# Zio_Ultrasonic_Distance_Sensor.net
KiCad netlist of a schematic drawn in EAGLE
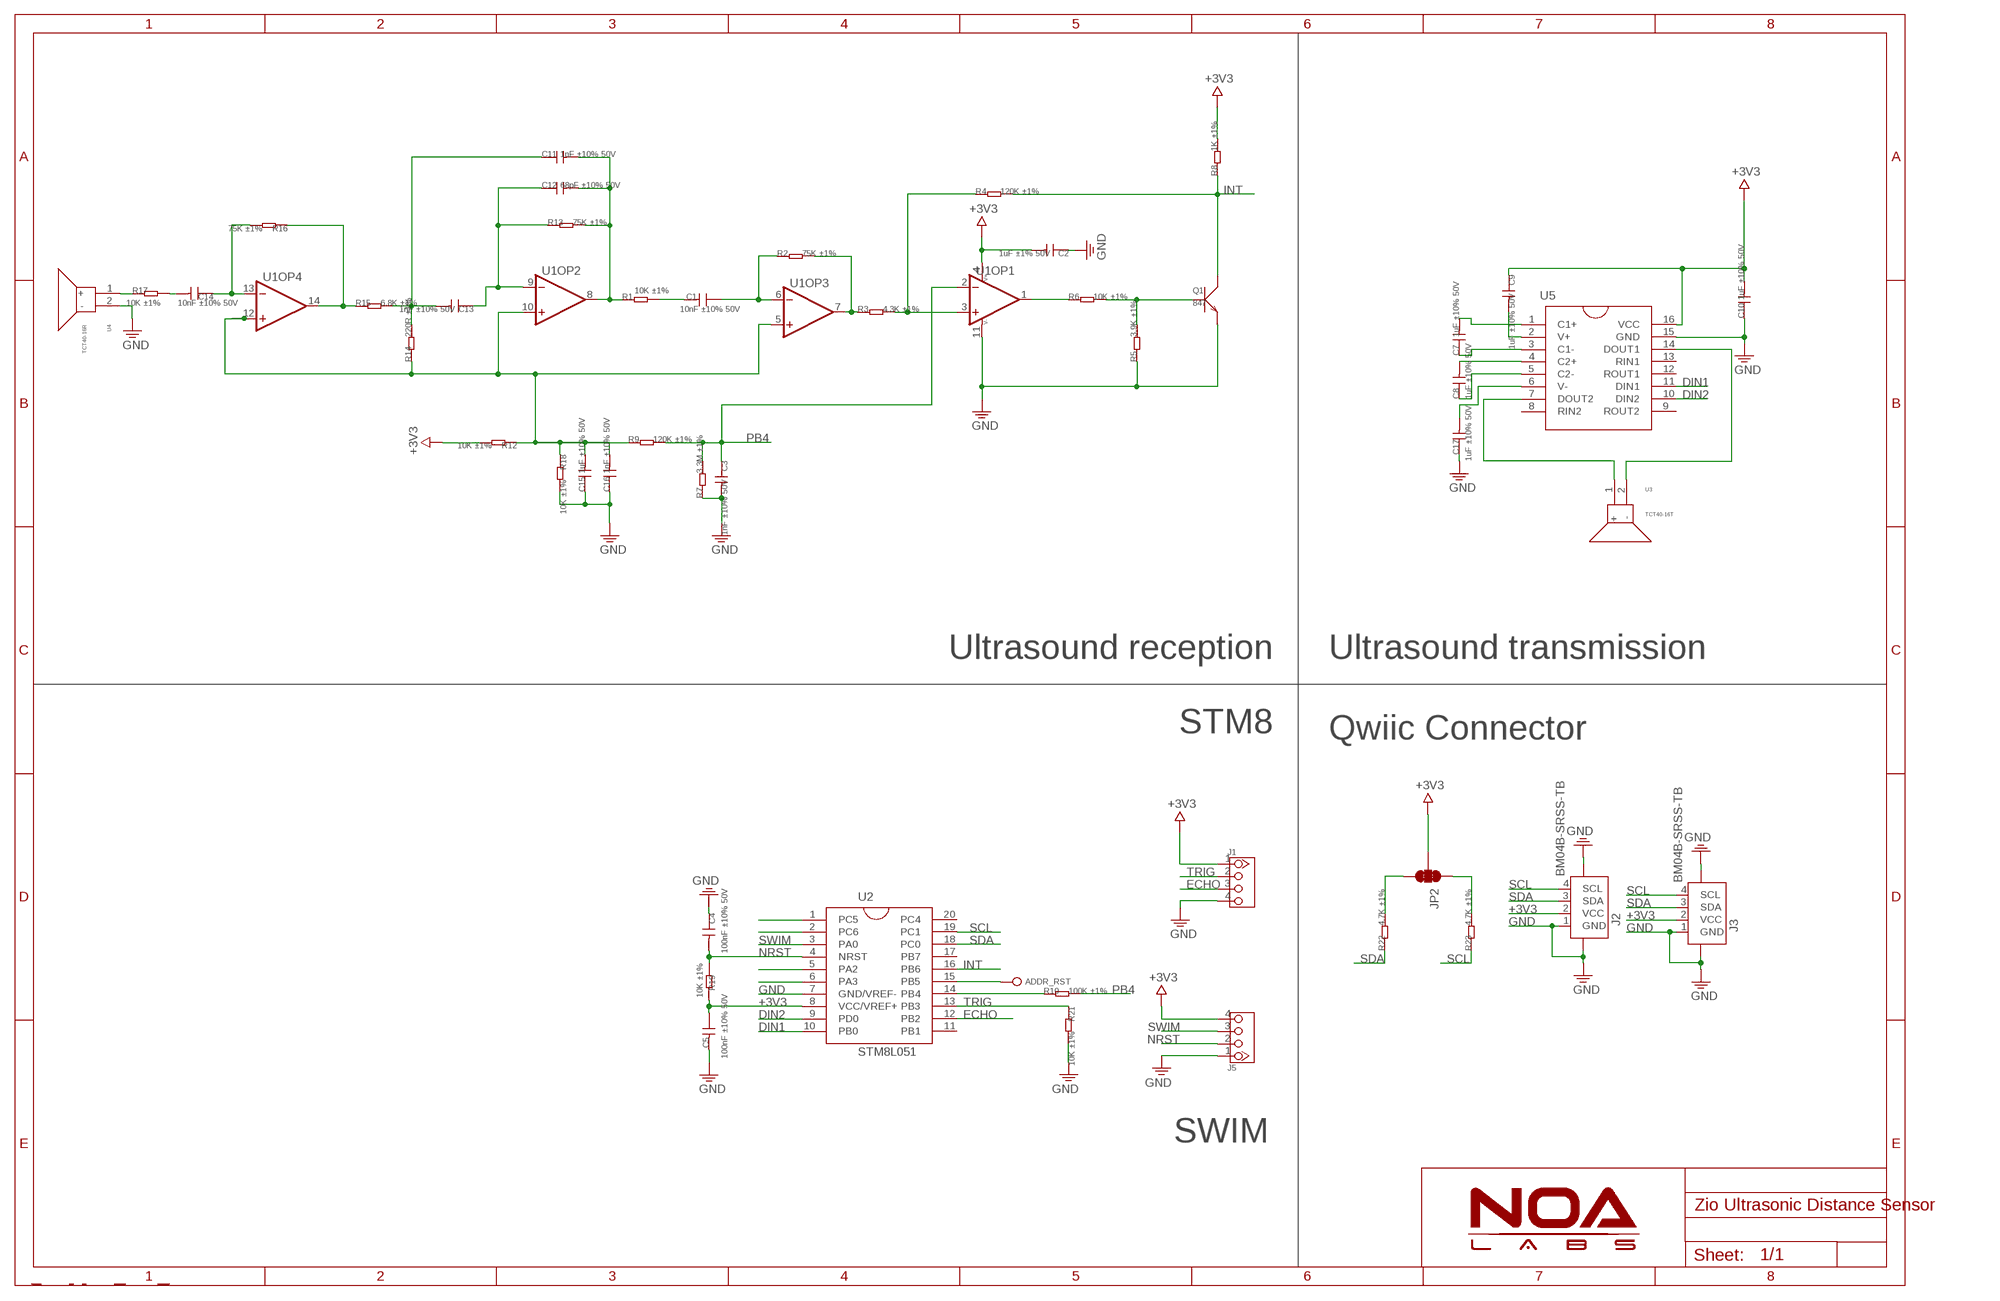
[diagram p0: schematic, sheet 1]

(export (version "E")
  (design (tool "Eeschema 10.0.6"))
  (components
    (comp (ref "ADDR_RST")
      (value "TEST_POINT35MIL")
      (footprint "eagle-import:1P-35MIL")
      (libsource (lib "eagle-import") (part "TEST_POINT35MIL"))
    )
    (comp (ref "C1")
      (value "10nF ±10% 50V")
      (footprint "eagle-import:0603")
      (libsource (lib "eagle-import") (part "C-0603"))
    )
    (comp (ref "C2")
      (value "1uF ±1% 50V")
      (footprint "eagle-import:0603")
      (libsource (lib "eagle-import") (part "C-0603"))
    )
    (comp (ref "C3")
      (value "1nF ±10% 50V")
      (footprint "eagle-import:0603")
      (libsource (lib "eagle-import") (part "C-0603"))
    )
    (comp (ref "C4")
      (value "100nF ±10% 50V")
      (footprint "eagle-import:0603")
      (libsource (lib "eagle-import") (part "C-0603"))
    )
    (comp (ref "C5")
      (value "100nF ±10% 50V")
      (footprint "eagle-import:0603")
      (libsource (lib "eagle-import") (part "C-0603"))
    )
    (comp (ref "C7")
      (value "1uF ±10% 50V")
      (footprint "eagle-import:0603")
      (libsource (lib "eagle-import") (part "C-0603"))
    )
    (comp (ref "C8")
      (value "1uF ±10% 50V")
      (footprint "eagle-import:0603")
      (libsource (lib "eagle-import") (part "C-0603"))
    )
    (comp (ref "C9")
      (value "1uF ±10% 50V")
      (footprint "eagle-import:0603")
      (libsource (lib "eagle-import") (part "C-0603"))
    )
    (comp (ref "C10")
      (value "1uF ±10% 50V")
      (footprint "eagle-import:0603")
      (libsource (lib "eagle-import") (part "C-0603"))
    )
    (comp (ref "C11")
      (value "1nF ±10% 50V")
      (footprint "eagle-import:0603")
      (libsource (lib "eagle-import") (part "C-0603"))
    )
    (comp (ref "C12")
      (value "68pF ±10% 50V")
      (footprint "eagle-import:0603")
      (libsource (lib "eagle-import") (part "C-0603"))
    )
    (comp (ref "C13")
      (value "1nF ±10% 50V")
      (footprint "eagle-import:0603")
      (libsource (lib "eagle-import") (part "C-0603"))
    )
    (comp (ref "C14")
      (value "10nF ±10% 50V")
      (footprint "eagle-import:0603")
      (libsource (lib "eagle-import") (part "C-0603"))
    )
    (comp (ref "C15")
      (value "1uF ±10% 50V")
      (footprint "eagle-import:0603")
      (libsource (lib "eagle-import") (part "C-0603"))
    )
    (comp (ref "C16")
      (value "1nF ±10% 50V")
      (footprint "eagle-import:0603")
      (libsource (lib "eagle-import") (part "C-0603"))
    )
    (comp (ref "C17")
      (value "1uF ±10% 50V")
      (footprint "eagle-import:0603")
      (libsource (lib "eagle-import") (part "C-0603"))
    )
    (comp (ref "J1")
      (value "HEADER-4P-60/35MIL")
      (footprint "eagle-import:4P-65_35MIL")
      (libsource (lib "eagle-import") (part "HEADER-4P-60/35MIL"))
    )
    (comp (ref "J2")
      (value "BM04B-SRSS-TB")
      (footprint "eagle-import:JST-SH-4P-90")
      (libsource (lib "eagle-import") (part "JST-SH-4P"))
    )
    (comp (ref "J3")
      (value "BM04B-SRSS-TB")
      (footprint "eagle-import:JST-SH-4P-90")
      (libsource (lib "eagle-import") (part "JST-SH-4P"))
    )
    (comp (ref "J5")
      (value "HEADER-4P-TEST_3.08_4P")
      (footprint "eagle-import:TEST_3.08_4P")
      (libsource (lib "eagle-import") (part "HEADER-4P-TEST_3.08_4P"))
    )
    (comp (ref "JP2")
      (value "SMT-JUMPER_3_2-NC_TRACE")
      (footprint "eagle-import:SMT-JUMPER_3_2-NC_TRACE")
      (libsource (lib "eagle-import") (part "SMT-JUMPER_3_2-NC_TRACE"))
    )
    (comp (ref "Q1")
      (value "847")
      (footprint "eagle-import:SOT23")
      (libsource (lib "eagle-import") (part "TRANSISTOR-NPN-SOT23''"))
    )
    (comp (ref "R1")
      (value "10K ±1%")
      (footprint "eagle-import:0603")
      (libsource (lib "eagle-import") (part "R-0603"))
    )
    (comp (ref "R2")
      (value "75K ±1%")
      (footprint "eagle-import:0603")
      (libsource (lib "eagle-import") (part "R-0603"))
    )
    (comp (ref "R3")
      (value "4.3K ±1%")
      (footprint "eagle-import:0603")
      (libsource (lib "eagle-import") (part "R-0603"))
    )
    (comp (ref "R4")
      (value "120K ±1%")
      (footprint "eagle-import:0603")
      (libsource (lib "eagle-import") (part "R-0603"))
    )
    (comp (ref "R5")
      (value "3.9K ±1%")
      (footprint "eagle-import:0603")
      (libsource (lib "eagle-import") (part "R-0603"))
    )
    (comp (ref "R6")
      (value "10K ±1%")
      (footprint "eagle-import:0603")
      (libsource (lib "eagle-import") (part "R-0603"))
    )
    (comp (ref "R7")
      (value "3.3M ±1%")
      (footprint "eagle-import:0603")
      (libsource (lib "eagle-import") (part "R-0603"))
    )
    (comp (ref "R8")
      (value "1K ±1%")
      (footprint "eagle-import:0603")
      (libsource (lib "eagle-import") (part "R-0603"))
    )
    (comp (ref "R9")
      (value "120K ±1%")
      (footprint "eagle-import:0603")
      (libsource (lib "eagle-import") (part "R-0603"))
    )
    (comp (ref "R10")
      (value "100K ±1%")
      (footprint "eagle-import:0603")
      (libsource (lib "eagle-import") (part "R-0603"))
    )
    (comp (ref "R12")
      (value "10K ±1%")
      (footprint "eagle-import:0603")
      (libsource (lib "eagle-import") (part "R-0603"))
    )
    (comp (ref "R13")
      (value "75K ±1%")
      (footprint "eagle-import:0603")
      (libsource (lib "eagle-import") (part "R-0603"))
    )
    (comp (ref "R14")
      (value "220R ±1%")
      (footprint "eagle-import:0603")
      (libsource (lib "eagle-import") (part "R-0603"))
    )
    (comp (ref "R15")
      (value "6.8K ±1%")
      (footprint "eagle-import:0603")
      (libsource (lib "eagle-import") (part "R-0603"))
    )
    (comp (ref "R16")
      (value "75K ±1%")
      (footprint "eagle-import:0603")
      (libsource (lib "eagle-import") (part "R-0603"))
    )
    (comp (ref "R17")
      (value "10K ±1%")
      (footprint "eagle-import:0603")
      (libsource (lib "eagle-import") (part "R-0603"))
    )
    (comp (ref "R18")
      (value "10K ±1%")
      (footprint "eagle-import:0603")
      (libsource (lib "eagle-import") (part "R-0603"))
    )
    (comp (ref "R19")
      (value "10K ±1%")
      (footprint "eagle-import:0603")
      (libsource (lib "eagle-import") (part "R-0603"))
    )
    (comp (ref "R21")
      (value "10K ±1%")
      (footprint "eagle-import:0603")
      (libsource (lib "eagle-import") (part "R-0603"))
    )
    (comp (ref "R22")
      (value "4.7K ±1%")
      (footprint "eagle-import:0603")
      (libsource (lib "eagle-import") (part "R-0603"))
    )
    (comp (ref "R23")
      (value "4.7K ±1%")
      (footprint "eagle-import:0603")
      (libsource (lib "eagle-import") (part "R-0603"))
    )
    (comp (ref "U1")
      (value "LMV324")
      (footprint "eagle-import:SO014")
      (libsource (lib "eagle-import") (part "LMV324"))
    )
    (comp (ref "U2")
      (value "STM8L051")
      (footprint "eagle-import:TSSOP20")
      (libsource (lib "eagle-import") (part "STM8L051"))
    )
    (comp (ref "U3")
      (value "TCT40-16T")
      (footprint "eagle-import:TCT40-16T_R")
      (libsource (lib "eagle-import") (part "TCT40-16T/R"))
    )
    (comp (ref "U4")
      (value "TCT40-16R")
      (footprint "eagle-import:TCT40-16T_R")
      (libsource (lib "eagle-import") (part "TCT40-16T/R"))
    )
    (comp (ref "U5")
      (value "UT3232G-S16-RSOIC-16")
      (footprint "eagle-import:SOIC16")
      (libsource (lib "eagle-import") (part "UT3232G-S16-RSOIC-16"))
    )
  )
  (nets
    (net (code "1") (name "+3V3") (class "Default")
      (node (ref "C10") (pin "2") (pinfunction "2_2") (pintype "passive"))
      (node (ref "C2") (pin "2") (pinfunction "2_2") (pintype "passive"))
      (node (ref "C5") (pin "1") (pinfunction "1_1") (pintype "passive"))
      (node (ref "C9") (pin "1") (pinfunction "1_1") (pintype "passive"))
      (node (ref "J1") (pin "1") (pinfunction "P$1_1") (pintype "bidirectional"))
      (node (ref "J2") (pin "2") (pinfunction "VCC_2") (pintype "bidirectional"))
      (node (ref "J3") (pin "2") (pinfunction "VCC_2") (pintype "bidirectional"))
      (node (ref "J5") (pin "4") (pinfunction "P$4_4") (pintype "bidirectional"))
      (node (ref "JP2") (pin "2") (pinfunction "2_2") (pintype "passive"))
      (node (ref "R12") (pin "2") (pinfunction "2_2") (pintype "passive"))
      (node (ref "R19") (pin "2") (pinfunction "2_2") (pintype "passive"))
      (node (ref "R8") (pin "2") (pinfunction "2_2") (pintype "passive"))
      (node (ref "U1") (pin "4") (pinfunction "V+_4") (pintype "power_in"))
      (node (ref "U2") (pin "8") (pinfunction "VCC/VREF+_8") (pintype "bidirectional"))
      (node (ref "U5") (pin "16") (pinfunction "VCC_16") (pintype "bidirectional"))
    )
    (net (code "2") (name "/DIN1") (class "Default")
      (node (ref "U2") (pin "10") (pinfunction "PB0_10") (pintype "bidirectional"))
      (node (ref "U5") (pin "11") (pinfunction "DIN1_11") (pintype "bidirectional"))
    )
    (net (code "3") (name "/DIN2") (class "Default")
      (node (ref "U2") (pin "9") (pinfunction "PD0_9") (pintype "bidirectional"))
      (node (ref "U5") (pin "10") (pinfunction "DIN2_10") (pintype "bidirectional"))
    )
    (net (code "4") (name "/ECHO") (class "Default")
      (node (ref "J1") (pin "3") (pinfunction "P$3_3") (pintype "bidirectional"))
      (node (ref "U2") (pin "12") (pinfunction "PB2_12") (pintype "bidirectional"))
    )
    (net (code "5") (name "/INT") (class "Default")
      (node (ref "Q1") (pin "3") (pinfunction "C_3") (pintype "passive"))
      (node (ref "R4") (pin "2") (pinfunction "2_2") (pintype "passive"))
      (node (ref "R8") (pin "1") (pinfunction "1_1") (pintype "passive"))
      (node (ref "U2") (pin "16") (pinfunction "PB6_16") (pintype "bidirectional"))
    )
    (net (code "6") (name "/NRST") (class "Default")
      (node (ref "C4") (pin "2") (pinfunction "2_2") (pintype "passive"))
      (node (ref "J5") (pin "2") (pinfunction "P$2_2") (pintype "bidirectional"))
      (node (ref "R19") (pin "1") (pinfunction "1_1") (pintype "passive"))
      (node (ref "U2") (pin "4") (pinfunction "NRST_4") (pintype "bidirectional"))
    )
    (net (code "7") (name "/PB4") (class "Default")
      (node (ref "C3") (pin "1") (pinfunction "1_1") (pintype "passive"))
      (node (ref "R10") (pin "2") (pinfunction "2_2") (pintype "passive"))
      (node (ref "R7") (pin "2") (pinfunction "2_2") (pintype "passive"))
      (node (ref "R9") (pin "2") (pinfunction "2_2") (pintype "passive"))
      (node (ref "U1") (pin "2") (pinfunction "IN-_2") (pintype "input"))
    )
    (net (code "8") (name "/SCL") (class "Default")
      (node (ref "J2") (pin "4") (pinfunction "SCL_4") (pintype "bidirectional"))
      (node (ref "J3") (pin "4") (pinfunction "SCL_4") (pintype "bidirectional"))
      (node (ref "R23") (pin "1") (pinfunction "1_1") (pintype "passive"))
      (node (ref "U2") (pin "19") (pinfunction "PC1_19") (pintype "bidirectional"))
    )
    (net (code "9") (name "/SDA") (class "Default")
      (node (ref "J2") (pin "3") (pinfunction "SDA_3") (pintype "bidirectional"))
      (node (ref "J3") (pin "3") (pinfunction "SDA_3") (pintype "bidirectional"))
      (node (ref "R22") (pin "1") (pinfunction "1_1") (pintype "passive"))
      (node (ref "U2") (pin "18") (pinfunction "PC0_18") (pintype "bidirectional"))
    )
    (net (code "10") (name "/SWIM") (class "Default")
      (node (ref "J5") (pin "3") (pinfunction "P$3_3") (pintype "bidirectional"))
      (node (ref "U2") (pin "3") (pinfunction "PA0_3") (pintype "bidirectional"))
    )
    (net (code "11") (name "/TRIG") (class "Default")
      (node (ref "J1") (pin "2") (pinfunction "P$2_2") (pintype "bidirectional"))
      (node (ref "R21") (pin "1") (pinfunction "1_1") (pintype "passive"))
      (node (ref "U2") (pin "13") (pinfunction "PB3_13") (pintype "bidirectional"))
    )
    (net (code "12") (name "GND") (class "Default")
      (node (ref "C10") (pin "1") (pinfunction "1_1") (pintype "passive"))
      (node (ref "C15") (pin "1") (pinfunction "1_1") (pintype "passive"))
      (node (ref "C16") (pin "1") (pinfunction "1_1") (pintype "passive"))
      (node (ref "C17") (pin "1") (pinfunction "1_1") (pintype "passive"))
      (node (ref "C2") (pin "1") (pinfunction "1_1") (pintype "passive"))
      (node (ref "C3") (pin "2") (pinfunction "2_2") (pintype "passive"))
      (node (ref "C4") (pin "1") (pinfunction "1_1") (pintype "passive"))
      (node (ref "C5") (pin "2") (pinfunction "2_2") (pintype "passive"))
      (node (ref "J1") (pin "4") (pinfunction "P$4_4") (pintype "bidirectional"))
      (node (ref "J2") (pin "1") (pinfunction "GND_1") (pintype "bidirectional"))
      (node (ref "J2") (pin "5") (pinfunction "5_5") (pintype "bidirectional"))
      (node (ref "J2") (pin "6") (pinfunction "6_6") (pintype "bidirectional"))
      (node (ref "J3") (pin "1") (pinfunction "GND_1") (pintype "bidirectional"))
      (node (ref "J3") (pin "5") (pinfunction "5_5") (pintype "bidirectional"))
      (node (ref "J3") (pin "6") (pinfunction "6_6") (pintype "bidirectional"))
      (node (ref "J5") (pin "1") (pinfunction "P$1_1") (pintype "bidirectional"))
      (node (ref "Q1") (pin "2") (pinfunction "E_2") (pintype "passive"))
      (node (ref "R18") (pin "2") (pinfunction "2_2") (pintype "passive"))
      (node (ref "R21") (pin "2") (pinfunction "2_2") (pintype "passive"))
      (node (ref "R5") (pin "1") (pinfunction "1_1") (pintype "passive"))
      (node (ref "R7") (pin "1") (pinfunction "1_1") (pintype "passive"))
      (node (ref "U1") (pin "11") (pinfunction "V-_11") (pintype "power_in"))
      (node (ref "U2") (pin "7") (pinfunction "GND/VREF-_7") (pintype "bidirectional"))
      (node (ref "U4") (pin "2") (pinfunction "-_2") (pintype "bidirectional"))
      (node (ref "U5") (pin "15") (pinfunction "GND_15") (pintype "bidirectional"))
    )
    (net (code "13") (name "Net-(ADDR_RST-1)") (class "Default")
      (node (ref "ADDR_RST") (pin "P$1") (pinfunction "1_P$1") (pintype "bidirectional"))
      (node (ref "U2") (pin "15") (pinfunction "PB5_15") (pintype "bidirectional"))
    )
    (net (code "14") (name "Net-(C1-Pad2)") (class "Default")
      (node (ref "C1") (pin "2") (pinfunction "2_2") (pintype "passive"))
      (node (ref "R1") (pin "2") (pinfunction "2_2") (pintype "passive"))
    )
    (net (code "15") (name "Net-(C11-Pad1)") (class "Default")
      (node (ref "C11") (pin "1") (pinfunction "1_1") (pintype "passive"))
      (node (ref "C13") (pin "2") (pinfunction "2_2") (pintype "passive"))
      (node (ref "R14") (pin "2") (pinfunction "2_2") (pintype "passive"))
      (node (ref "R15") (pin "2") (pinfunction "2_2") (pintype "passive"))
    )
    (net (code "16") (name "Net-(C14-Pad2)") (class "Default")
      (node (ref "C14") (pin "2") (pinfunction "2_2") (pintype "passive"))
      (node (ref "R17") (pin "2") (pinfunction "2_2") (pintype "passive"))
    )
    (net (code "17") (name "Net-(JP2-Pad1)") (class "Default")
      (node (ref "JP2") (pin "1") (pinfunction "1_1") (pintype "passive"))
      (node (ref "R23") (pin "2") (pinfunction "2_2") (pintype "passive"))
    )
    (net (code "18") (name "Net-(JP2-Pad3)") (class "Default")
      (node (ref "JP2") (pin "3") (pinfunction "3_3") (pintype "passive"))
      (node (ref "R22") (pin "2") (pinfunction "2_2") (pintype "passive"))
    )
    (net (code "19") (name "Net-(Q1-B)") (class "Default")
      (node (ref "Q1") (pin "1") (pinfunction "B_1") (pintype "passive"))
      (node (ref "R5") (pin "2") (pinfunction "2_2") (pintype "passive"))
      (node (ref "R6") (pin "2") (pinfunction "2_2") (pintype "passive"))
    )
    (net (code "20") (name "Net-(U1A-IN+)") (class "Default")
      (node (ref "R3") (pin "2") (pinfunction "2_2") (pintype "passive"))
      (node (ref "R4") (pin "1") (pinfunction "1_1") (pintype "passive"))
      (node (ref "U1") (pin "3") (pinfunction "IN+_3") (pintype "input"))
    )
    (net (code "21") (name "Net-(U1A-OUT)") (class "Default")
      (node (ref "R6") (pin "1") (pinfunction "1_1") (pintype "passive"))
      (node (ref "U1") (pin "1") (pinfunction "OUT_1") (pintype "output"))
    )
    (net (code "22") (name "Net-(U1B-IN+)") (class "Default")
      (node (ref "C15") (pin "2") (pinfunction "2_2") (pintype "passive"))
      (node (ref "C16") (pin "2") (pinfunction "2_2") (pintype "passive"))
      (node (ref "R12") (pin "1") (pinfunction "1_1") (pintype "passive"))
      (node (ref "R14") (pin "1") (pinfunction "1_1") (pintype "passive"))
      (node (ref "R18") (pin "1") (pinfunction "1_1") (pintype "passive"))
      (node (ref "R9") (pin "1") (pinfunction "1_1") (pintype "passive"))
      (node (ref "U1") (pin "10") (pinfunction "IN+_10") (pintype "input"))
      (node (ref "U1") (pin "12") (pinfunction "IN+_12") (pintype "input"))
      (node (ref "U1") (pin "5") (pinfunction "IN+_5") (pintype "input"))
    )
    (net (code "23") (name "Net-(U1B-IN-)") (class "Default")
      (node (ref "C12") (pin "1") (pinfunction "1_1") (pintype "passive"))
      (node (ref "C13") (pin "1") (pinfunction "1_1") (pintype "passive"))
      (node (ref "R13") (pin "1") (pinfunction "1_1") (pintype "passive"))
      (node (ref "U1") (pin "9") (pinfunction "IN-_9") (pintype "input"))
    )
    (net (code "24") (name "Net-(U1B-OUT)") (class "Default")
      (node (ref "C11") (pin "2") (pinfunction "2_2") (pintype "passive"))
      (node (ref "C12") (pin "2") (pinfunction "2_2") (pintype "passive"))
      (node (ref "R1") (pin "1") (pinfunction "1_1") (pintype "passive"))
      (node (ref "R13") (pin "2") (pinfunction "2_2") (pintype "passive"))
      (node (ref "U1") (pin "8") (pinfunction "OUT_8") (pintype "output"))
    )
    (net (code "25") (name "Net-(U1C-IN-)") (class "Default")
      (node (ref "C1") (pin "1") (pinfunction "1_1") (pintype "passive"))
      (node (ref "R2") (pin "1") (pinfunction "1_1") (pintype "passive"))
      (node (ref "U1") (pin "6") (pinfunction "IN-_6") (pintype "input"))
    )
    (net (code "26") (name "Net-(U1C-OUT)") (class "Default")
      (node (ref "R2") (pin "2") (pinfunction "2_2") (pintype "passive"))
      (node (ref "R3") (pin "1") (pinfunction "1_1") (pintype "passive"))
      (node (ref "U1") (pin "7") (pinfunction "OUT_7") (pintype "output"))
    )
    (net (code "27") (name "Net-(U1D-IN-)") (class "Default")
      (node (ref "C14") (pin "1") (pinfunction "1_1") (pintype "passive"))
      (node (ref "R16") (pin "2") (pinfunction "2_2") (pintype "passive"))
      (node (ref "U1") (pin "13") (pinfunction "IN-_13") (pintype "input"))
    )
    (net (code "28") (name "Net-(U1D-OUT)") (class "Default")
      (node (ref "R15") (pin "1") (pinfunction "1_1") (pintype "passive"))
      (node (ref "R16") (pin "1") (pinfunction "1_1") (pintype "passive"))
      (node (ref "U1") (pin "14") (pinfunction "OUT_14") (pintype "output"))
    )
    (net (code "29") (name "Net-(U2-PB4)") (class "Default")
      (node (ref "R10") (pin "1") (pinfunction "1_1") (pintype "passive"))
      (node (ref "U2") (pin "14") (pinfunction "PB4_14") (pintype "bidirectional"))
    )
    (net (code "30") (name "Net-(U3-+)") (class "Default")
      (node (ref "U3") (pin "1") (pinfunction "+_1") (pintype "bidirectional"))
      (node (ref "U5") (pin "7") (pinfunction "DOUT2_7") (pintype "bidirectional"))
    )
    (net (code "31") (name "Net-(U3--)") (class "Default")
      (node (ref "U3") (pin "2") (pinfunction "-_2") (pintype "bidirectional"))
      (node (ref "U5") (pin "14") (pinfunction "DOUT1_14") (pintype "bidirectional"))
    )
    (net (code "32") (name "Net-(U4-+)") (class "Default")
      (node (ref "R17") (pin "1") (pinfunction "1_1") (pintype "passive"))
      (node (ref "U4") (pin "1") (pinfunction "+_1") (pintype "bidirectional"))
    )
    (net (code "33") (name "Net-(U5-C1+)") (class "Default")
      (node (ref "C7") (pin "2") (pinfunction "2_2") (pintype "passive"))
      (node (ref "U5") (pin "1") (pinfunction "C1+_1") (pintype "bidirectional"))
    )
    (net (code "34") (name "Net-(U5-C1-)") (class "Default")
      (node (ref "C7") (pin "1") (pinfunction "1_1") (pintype "passive"))
      (node (ref "U5") (pin "3") (pinfunction "C1-_3") (pintype "bidirectional"))
    )
    (net (code "35") (name "Net-(U5-C2+)") (class "Default")
      (node (ref "C8") (pin "2") (pinfunction "2_2") (pintype "passive"))
      (node (ref "U5") (pin "4") (pinfunction "C2+_4") (pintype "bidirectional"))
    )
    (net (code "36") (name "Net-(U5-C2-)") (class "Default")
      (node (ref "C8") (pin "1") (pinfunction "1_1") (pintype "passive"))
      (node (ref "U5") (pin "5") (pinfunction "C2-_5") (pintype "bidirectional"))
    )
    (net (code "37") (name "Net-(U5-V+)") (class "Default")
      (node (ref "C9") (pin "2") (pinfunction "2_2") (pintype "passive"))
      (node (ref "U5") (pin "2") (pinfunction "V+_2") (pintype "bidirectional"))
    )
    (net (code "38") (name "Net-(U5-V-)") (class "Default")
      (node (ref "C17") (pin "2") (pinfunction "2_2") (pintype "passive"))
      (node (ref "U5") (pin "6") (pinfunction "V-_6") (pintype "bidirectional"))
    )
    (net (code "39") (name "unconnected-(U2-PA2-Pad5)") (class "Default")
      (node (ref "U2") (pin "5") (pinfunction "PA2_5") (pintype "bidirectional"))
    )
    (net (code "40") (name "unconnected-(U2-PA3-Pad6)") (class "Default")
      (node (ref "U2") (pin "6") (pinfunction "PA3_6") (pintype "bidirectional"))
    )
    (net (code "41") (name "unconnected-(U2-PB1-Pad11)") (class "Default")
      (node (ref "U2") (pin "11") (pinfunction "PB1_11") (pintype "bidirectional"))
    )
    (net (code "42") (name "unconnected-(U2-PB7-Pad17)") (class "Default")
      (node (ref "U2") (pin "17") (pinfunction "PB7_17") (pintype "bidirectional"))
    )
    (net (code "43") (name "unconnected-(U2-PC4-Pad20)") (class "Default")
      (node (ref "U2") (pin "20") (pinfunction "PC4_20") (pintype "bidirectional"))
    )
    (net (code "44") (name "unconnected-(U2-PC5-Pad1)") (class "Default")
      (node (ref "U2") (pin "1") (pinfunction "PC5_1") (pintype "bidirectional"))
    )
    (net (code "45") (name "unconnected-(U2-PC6-Pad2)") (class "Default")
      (node (ref "U2") (pin "2") (pinfunction "PC6_2") (pintype "bidirectional"))
    )
    (net (code "46") (name "unconnected-(U5-RIN1-Pad13)") (class "Default")
      (node (ref "U5") (pin "13") (pinfunction "RIN1_13") (pintype "bidirectional"))
    )
    (net (code "47") (name "unconnected-(U5-RIN2-Pad8)") (class "Default")
      (node (ref "U5") (pin "8") (pinfunction "RIN2_8") (pintype "bidirectional"))
    )
    (net (code "48") (name "unconnected-(U5-ROUT1-Pad12)") (class "Default")
      (node (ref "U5") (pin "12") (pinfunction "ROUT1_12") (pintype "bidirectional"))
    )
    (net (code "49") (name "unconnected-(U5-ROUT2-Pad9)") (class "Default")
      (node (ref "U5") (pin "9") (pinfunction "ROUT2_9") (pintype "bidirectional"))
    )
  )
)
